# design.net
KiCad netlist of a schematic drawn in Altium Designer
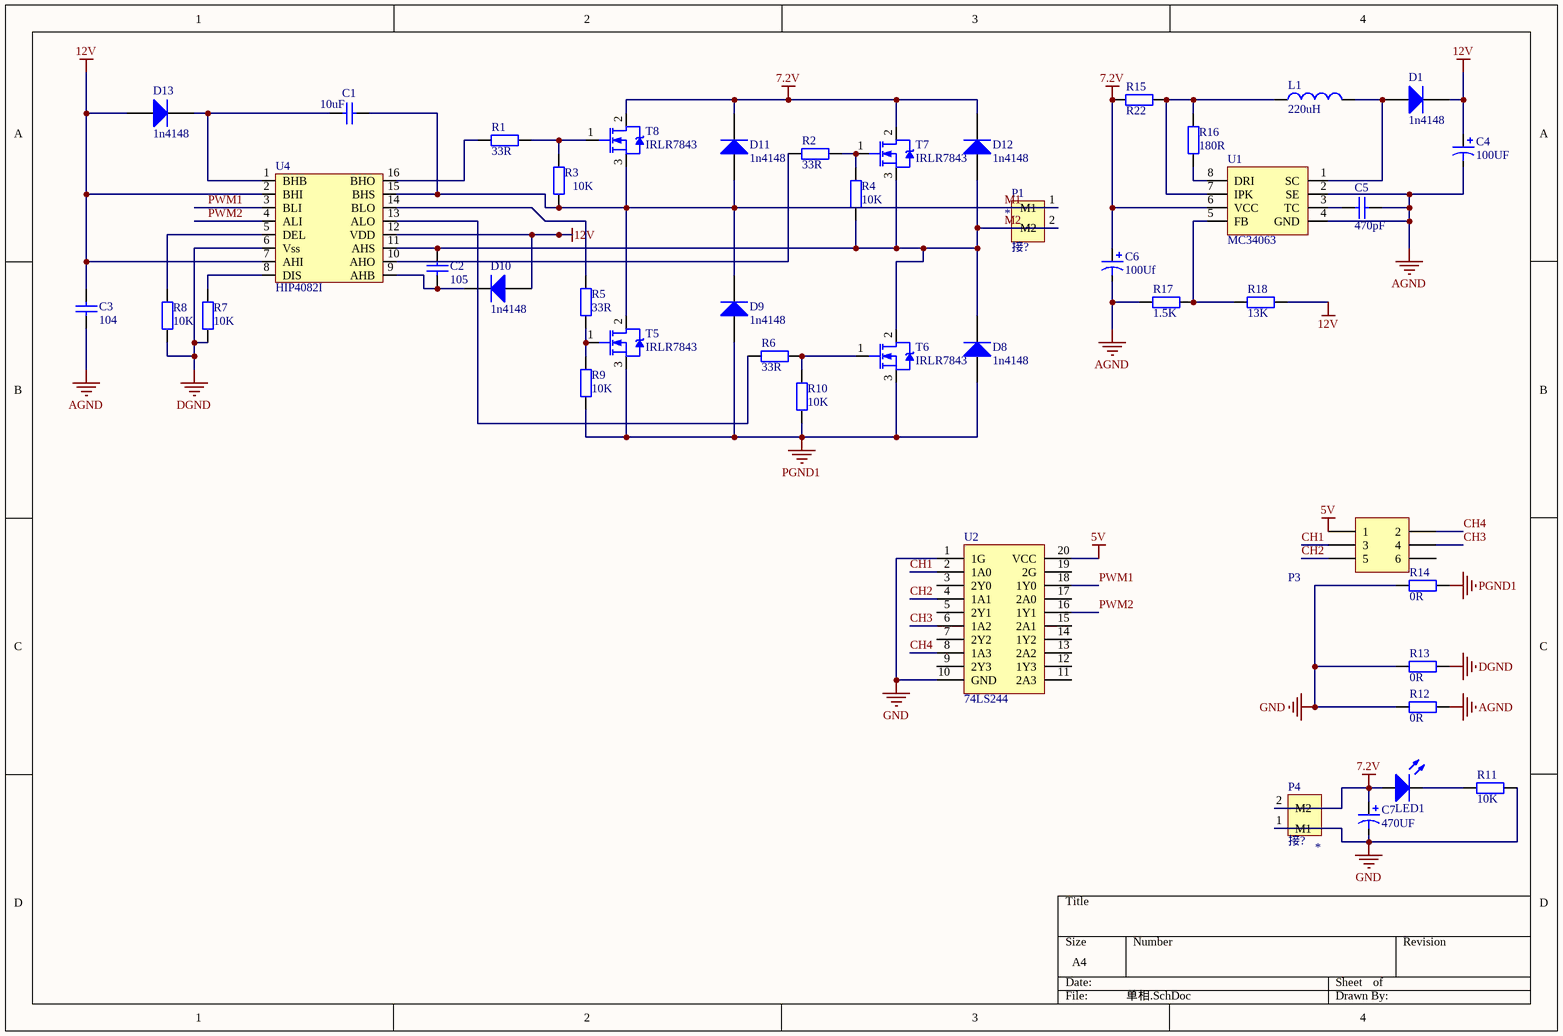
[diagram p0: 单相.SchDoc]

(export (version "E")
  (design (tool "Eeschema 10.0.6"))
  (components
    (comp (ref "C1")
      (value "10uF")
      (footprint "0805")
      (description "无极电容")
      (fields (field (name "Comment") "105"))
      (libsource (lib "JMU智能车专用3.0.6") (part "Cap"))
    )
    (comp (ref "C2")
      (value "105")
      (footprint "0805")
      (description "无极电容")
      (libsource (lib "JMU智能车专用3.0.6") (part "Cap"))
    )
    (comp (ref "C3")
      (value "104")
      (footprint "0805")
      (description "无极电容")
      (libsource (lib "JMU智能车专用3.0.6") (part "Cap"))
    )
    (comp (ref "C4")
      (value "100UF")
      (footprint "ED6.3")
      (description "通用有极电容")
      (libsource (lib "JMU智能车专用3.0.6") (part "pol cap"))
    )
    (comp (ref "C5")
      (value "470pF")
      (footprint "0805")
      (description "无极电容")
      (libsource (lib "JMU智能车专用3.0.6") (part "Cap"))
    )
    (comp (ref "C6")
      (value "100Uf")
      (footprint "ED6.3")
      (description "通用有极电容")
      (libsource (lib "JMU智能车专用3.0.6") (part "pol cap"))
    )
    (comp (ref "C7")
      (value "470UF")
      (footprint "ED8")
      (description "通用有极电容")
      (libsource (lib "JMU智能车专用3.0.6") (part "pol cap"))
    )
    (comp (ref "D1") (value "1n4148") (libsource (lib "zaji") (part "1n4148")))
    (comp (ref "D8") (value "1n4148") (libsource (lib "zaji") (part "1n4148")))
    (comp (ref "D9") (value "1n4148") (libsource (lib "zaji") (part "1n4148")))
    (comp (ref "D10") (value "1n4148") (libsource (lib "zaji") (part "1n4148")))
    (comp (ref "D11") (value "1n4148") (libsource (lib "zaji") (part "1n4148")))
    (comp (ref "D12") (value "1n4148") (libsource (lib "zaji") (part "1n4148")))
    (comp (ref "D13") (value "1n4148") (libsource (lib "zaji") (part "1n4148")))
    (comp (ref "L1")
      (value "220uH")
      (footprint "电感（220uh）")
      (description "7*7*4")
      (libsource (lib "JMU智能车专用3.0.6") (part "电感 220uh"))
    )
    (comp (ref "LED1")
      (value "LED")
      (footprint "LED(0805)")
      (description "发光二极管")
      (libsource (lib "JMU智能车专用3.0.6") (part "LED"))
    )
    (comp (ref "P1")
      (value "*")
      (fields (field (name "ALTIUM_UNNAMED_3") "接?"))
      (libsource (lib "JMU智能车专用") (part "接线端子"))
    )
    (comp (ref "P3")
      (value "Header 3X2")
      (footprint "HDR2X3")
      (description "Header, 3-Pin, Dual row")
      (fields (field (name "PUBLISHER") "Altium Limited"))
      (libsource (lib "Miscellaneous Connectors") (part "Header 3X2"))
    )
    (comp (ref "P4")
      (value "*")
      (fields (field (name "ALTIUM_UNNAMED_3") "接?"))
      (libsource (lib "") (part "接线端子_1"))
    )
    (comp (ref "R1")
      (value "33R")
      (footprint "0805")
      (description "通用电阻")
      (libsource (lib "") (part "Res_2"))
    )
    (comp (ref "R2")
      (value "33R")
      (footprint "0805")
      (description "通用电阻")
      (libsource (lib "") (part "Res_1"))
    )
    (comp (ref "R3")
      (value "10K")
      (footprint "0805")
      (description "通用电阻")
      (libsource (lib "JMU智能车专用") (part "Res"))
    )
    (comp (ref "R4")
      (value "10K")
      (footprint "0805")
      (description "通用电阻")
      (libsource (lib "JMU智能车专用") (part "Res"))
    )
    (comp (ref "R5")
      (value "33R")
      (footprint "0805")
      (description "通用电阻")
      (libsource (lib "") (part "Res_3"))
    )
    (comp (ref "R6")
      (value "33R")
      (footprint "0805")
      (description "通用电阻")
      (libsource (lib "") (part "Res_1"))
    )
    (comp (ref "R7")
      (value "10K")
      (footprint "0805")
      (description "通用电阻")
      (libsource (lib "") (part "Res_3"))
    )
    (comp (ref "R8")
      (value "10K")
      (footprint "0805")
      (description "通用电阻")
      (libsource (lib "") (part "Res_3"))
    )
    (comp (ref "R9")
      (value "10K")
      (footprint "0805")
      (description "通用电阻")
      (libsource (lib "JMU智能车专用") (part "Res"))
    )
    (comp (ref "R10")
      (value "10K")
      (footprint "0805")
      (description "通用电阻")
      (libsource (lib "") (part "Res_3"))
    )
    (comp (ref "R11")
      (value "10K")
      (footprint "0603")
      (description "通用电阻")
      (libsource (lib "") (part "Res_1"))
    )
    (comp (ref "R12")
      (value "0R")
      (footprint "0805")
      (description "通用电阻")
      (libsource (lib "") (part "Res_2"))
    )
    (comp (ref "R13")
      (value "0R")
      (footprint "0805")
      (description "通用电阻")
      (libsource (lib "") (part "Res_2"))
    )
    (comp (ref "R14")
      (value "0R")
      (footprint "0805")
      (description "通用电阻")
      (libsource (lib "") (part "Res_2"))
    )
    (comp (ref "R15")
      (value "R22")
      (footprint "0805")
      (description "通用电阻")
      (libsource (lib "JMU智能车专用3.0.6") (part "Res"))
    )
    (comp (ref "R16")
      (value "180R")
      (footprint "0805")
      (description "通用电阻")
      (libsource (lib "") (part "Res_2"))
    )
    (comp (ref "R17")
      (value "1.5K")
      (footprint "0805")
      (description "通用电阻")
      (libsource (lib "JMU智能车专用3.0.6") (part "Res"))
    )
    (comp (ref "R18")
      (value "13K")
      (footprint "0805")
      (description "通用电阻")
      (libsource (lib "JMU智能车专用3.0.6") (part "Res"))
    )
    (comp (ref "T5")
      (value "IRLR7843")
      (footprint "IRLR7843(MOS)")
      (libsource (lib "JMU智能车专用") (part "N_MOS(IRLR7843)"))
    )
    (comp (ref "T6")
      (value "IRLR7843")
      (footprint "IRLR7843(MOS)")
      (libsource (lib "JMU智能车专用") (part "N_MOS(IRLR7843)"))
    )
    (comp (ref "T7")
      (value "IRLR7843")
      (footprint "IRLR7843(MOS)")
      (libsource (lib "JMU智能车专用") (part "N_MOS(IRLR7843)"))
    )
    (comp (ref "T8")
      (value "IRLR7843")
      (footprint "IRLR7843(MOS)")
      (libsource (lib "JMU智能车专用") (part "N_MOS(IRLR7843)"))
    )
    (comp (ref "U1")
      (value "MC34063")
      (footprint "MA34063")
      (libsource (lib "JMU智能车专用3.0.6") (part "MC34063"))
    )
    (comp (ref "U2")
      (value "74LS244")
      (footprint "74LS244D")
      (libsource (lib "JMU智能车专用3.0.6") (part "74LS244"))
    )
    (comp (ref "U4") (value "HIP4082I") (footprint "HIP4082I") (libsource (lib "JMU智能车专用") (part "HIP4082I")))
  )
  (nets
    (net (code "1") (name "/CH1") (class "Default")
      (node (ref "P3") (pin "3") (pinfunction "3_3") (pintype "passive"))
      (node (ref "U2") (pin "2") (pinfunction "1A0_2") (pintype "passive"))
    )
    (net (code "2") (name "/CH2") (class "Default")
      (node (ref "P3") (pin "5") (pinfunction "5_5") (pintype "passive"))
      (node (ref "U2") (pin "4") (pinfunction "1A1_4") (pintype "passive"))
    )
    (net (code "3") (name "/CH3") (class "Default")
      (node (ref "P3") (pin "4") (pinfunction "4_4") (pintype "passive"))
      (node (ref "U2") (pin "6") (pinfunction "1A2_6") (pintype "passive"))
    )
    (net (code "4") (name "/CH4") (class "Default")
      (node (ref "P3") (pin "2") (pinfunction "2_2") (pintype "passive"))
      (node (ref "U2") (pin "8") (pinfunction "1A3_8") (pintype "passive"))
    )
    (net (code "5") (name "/M1") (class "Default")
      (node (ref "C1") (pin "2") (pinfunction "2_2") (pintype "passive"))
      (node (ref "D11") (pin "1") (pinfunction "A_1") (pintype "passive"))
      (node (ref "D9") (pin "2") (pinfunction "K_2") (pintype "passive"))
      (node (ref "P1") (pin "1") (pinfunction "M1_1") (pintype "passive"))
      (node (ref "R3") (pin "2") (pinfunction "2_2") (pintype "passive"))
      (node (ref "T5") (pin "2") (pinfunction "D_2") (pintype "passive"))
      (node (ref "T8") (pin "3") (pinfunction "S_3") (pintype "passive"))
      (node (ref "U4") (pin "15") (pinfunction "BHS_15") (pintype "passive"))
    )
    (net (code "6") (name "/M2") (class "Default")
      (node (ref "C2") (pin "2") (pinfunction "2_2") (pintype "passive"))
      (node (ref "D12") (pin "1") (pinfunction "A_1") (pintype "passive"))
      (node (ref "D8") (pin "2") (pinfunction "K_2") (pintype "passive"))
      (node (ref "P1") (pin "2") (pinfunction "M2_2") (pintype "passive"))
      (node (ref "R4") (pin "2") (pinfunction "2_2") (pintype "passive"))
      (node (ref "T6") (pin "2") (pinfunction "D_2") (pintype "passive"))
      (node (ref "T7") (pin "3") (pinfunction "S_3") (pintype "passive"))
      (node (ref "U4") (pin "11") (pinfunction "AHS_11") (pintype "passive"))
    )
    (net (code "7") (name "/PWM1") (class "Default")
      (node (ref "U2") (pin "18") (pinfunction "1Y0_18") (pintype "passive"))
      (node (ref "U4") (pin "3") (pinfunction "BLI_3") (pintype "passive"))
    )
    (net (code "8") (name "/PWM2") (class "Default")
      (node (ref "U2") (pin "16") (pinfunction "1Y1_16") (pintype "passive"))
      (node (ref "U4") (pin "4") (pinfunction "ALI_4") (pintype "passive"))
    )
    (net (code "9") (name "5V") (class "Default")
      (node (ref "P3") (pin "1") (pinfunction "1_1") (pintype "passive"))
      (node (ref "U2") (pin "20") (pinfunction "VCC_20") (pintype "passive"))
    )
    (net (code "10") (name "7.2V") (class "Default")
      (node (ref "C6") (pin "1") (pinfunction "1_1") (pintype "passive"))
      (node (ref "C7") (pin "1") (pinfunction "1_1") (pintype "passive"))
      (node (ref "D11") (pin "2") (pinfunction "K_2") (pintype "passive"))
      (node (ref "D12") (pin "2") (pinfunction "K_2") (pintype "passive"))
      (node (ref "LED1") (pin "1") (pinfunction "A_1") (pintype "passive"))
      (node (ref "P4") (pin "2") (pinfunction "M2_2") (pintype "passive"))
      (node (ref "R15") (pin "1") (pinfunction "1_1") (pintype "passive"))
      (node (ref "T7") (pin "2") (pinfunction "D_2") (pintype "passive"))
      (node (ref "T8") (pin "2") (pinfunction "D_2") (pintype "passive"))
      (node (ref "U1") (pin "6") (pinfunction "VCC_6") (pintype "passive"))
    )
    (net (code "11") (name "12V") (class "Default")
      (node (ref "C3") (pin "2") (pinfunction "2_2") (pintype "passive"))
      (node (ref "C4") (pin "1") (pinfunction "1_1") (pintype "passive"))
      (node (ref "D1") (pin "2") (pinfunction "K_2") (pintype "passive"))
      (node (ref "D10") (pin "1") (pinfunction "A_1") (pintype "passive"))
      (node (ref "D13") (pin "1") (pinfunction "A_1") (pintype "passive"))
      (node (ref "R18") (pin "2") (pinfunction "2_2") (pintype "passive"))
      (node (ref "U4") (pin "12") (pinfunction "VDD_12") (pintype "passive"))
      (node (ref "U4") (pin "2") (pinfunction "BHI_2") (pintype "passive"))
      (node (ref "U4") (pin "7") (pinfunction "AHI_7") (pintype "passive"))
    )
    (net (code "12") (name "AGND") (class "Default")
      (node (ref "C3") (pin "1") (pinfunction "1_1") (pintype "passive"))
      (node (ref "C4") (pin "2") (pinfunction "2_2") (pintype "passive"))
      (node (ref "C5") (pin "1") (pinfunction "1_1") (pintype "passive"))
      (node (ref "C6") (pin "2") (pinfunction "2_2") (pintype "passive"))
      (node (ref "R12") (pin "2") (pinfunction "2_2") (pintype "passive"))
      (node (ref "R17") (pin "1") (pinfunction "1_1") (pintype "passive"))
      (node (ref "U1") (pin "2") (pinfunction "SE_2") (pintype "passive"))
      (node (ref "U1") (pin "4") (pinfunction "GND_4") (pintype "passive"))
    )
    (net (code "13") (name "DGND") (class "Default")
      (node (ref "R13") (pin "2") (pinfunction "2_2") (pintype "passive"))
      (node (ref "R7") (pin "1") (pinfunction "1_1") (pintype "passive"))
      (node (ref "R8") (pin "1") (pinfunction "1_1") (pintype "passive"))
      (node (ref "U4") (pin "6") (pinfunction "Vss_6") (pintype "passive"))
    )
    (net (code "14") (name "GND") (class "Default")
      (node (ref "C7") (pin "2") (pinfunction "2_2") (pintype "passive"))
      (node (ref "P4") (pin "1") (pinfunction "M1_1") (pintype "passive"))
      (node (ref "R11") (pin "1") (pinfunction "1_1") (pintype "passive"))
      (node (ref "R12") (pin "1") (pinfunction "1_1") (pintype "passive"))
      (node (ref "R13") (pin "1") (pinfunction "1_1") (pintype "passive"))
      (node (ref "R14") (pin "1") (pinfunction "1_1") (pintype "passive"))
      (node (ref "U2") (pin "1") (pinfunction "1G_1") (pintype "passive"))
      (node (ref "U2") (pin "10") (pinfunction "GND_10") (pintype "passive"))
    )
    (net (code "15") (name "Net-(D1-A)") (class "Default")
      (node (ref "D1") (pin "1") (pinfunction "A_1") (pintype "passive"))
      (node (ref "L1") (pin "2") (pinfunction "2_2") (pintype "passive"))
      (node (ref "U1") (pin "1") (pinfunction "SC_1") (pintype "passive"))
    )
    (net (code "16") (name "Net-(D10-K)") (class "Default")
      (node (ref "C2") (pin "1") (pinfunction "1_1") (pintype "passive"))
      (node (ref "D10") (pin "2") (pinfunction "K_2") (pintype "passive"))
      (node (ref "U4") (pin "9") (pinfunction "AHB_9") (pintype "passive"))
    )
    (net (code "17") (name "Net-(D13-K)") (class "Default")
      (node (ref "C1") (pin "1") (pinfunction "1_1") (pintype "passive"))
      (node (ref "D13") (pin "2") (pinfunction "K_2") (pintype "passive"))
      (node (ref "U4") (pin "1") (pinfunction "BHB_1") (pintype "passive"))
    )
    (net (code "18") (name "Net-(LED1-K)") (class "Default")
      (node (ref "LED1") (pin "2") (pinfunction "K_2") (pintype "passive"))
      (node (ref "R11") (pin "2") (pinfunction "2_2") (pintype "passive"))
    )
    (net (code "19") (name "Net-(T5-G)") (class "Default")
      (node (ref "R5") (pin "1") (pinfunction "1_1") (pintype "passive"))
      (node (ref "R9") (pin "1") (pinfunction "1_1") (pintype "passive"))
      (node (ref "T5") (pin "1") (pinfunction "G_1") (pintype "passive"))
    )
    (net (code "20") (name "Net-(T6-G)") (class "Default")
      (node (ref "R10") (pin "2") (pinfunction "2_2") (pintype "passive"))
      (node (ref "R6") (pin "1") (pinfunction "1_1") (pintype "passive"))
      (node (ref "T6") (pin "1") (pinfunction "G_1") (pintype "passive"))
    )
    (net (code "21") (name "Net-(T7-G)") (class "Default")
      (node (ref "R2") (pin "1") (pinfunction "1_1") (pintype "passive"))
      (node (ref "R4") (pin "1") (pinfunction "1_1") (pintype "passive"))
      (node (ref "T7") (pin "1") (pinfunction "G_1") (pintype "passive"))
    )
    (net (code "22") (name "Net-(T8-G)") (class "Default")
      (node (ref "R1") (pin "2") (pinfunction "2_2") (pintype "passive"))
      (node (ref "R3") (pin "1") (pinfunction "1_1") (pintype "passive"))
      (node (ref "T8") (pin "1") (pinfunction "G_1") (pintype "passive"))
    )
    (net (code "23") (name "Net-(U1-DRI)") (class "Default")
      (node (ref "R16") (pin "1") (pinfunction "1_1") (pintype "passive"))
      (node (ref "U1") (pin "8") (pinfunction "DRI_8") (pintype "passive"))
    )
    (net (code "24") (name "Net-(U1-FB)") (class "Default")
      (node (ref "R17") (pin "2") (pinfunction "2_2") (pintype "passive"))
      (node (ref "R18") (pin "1") (pinfunction "1_1") (pintype "passive"))
      (node (ref "U1") (pin "5") (pinfunction "FB_5") (pintype "passive"))
    )
    (net (code "25") (name "Net-(U1-IPK)") (class "Default")
      (node (ref "L1") (pin "1") (pinfunction "1_1") (pintype "passive"))
      (node (ref "R15") (pin "2") (pinfunction "2_2") (pintype "passive"))
      (node (ref "R16") (pin "2") (pinfunction "2_2") (pintype "passive"))
      (node (ref "U1") (pin "7") (pinfunction "IPK_7") (pintype "passive"))
    )
    (net (code "26") (name "Net-(U1-TC)") (class "Default")
      (node (ref "C5") (pin "2") (pinfunction "2_2") (pintype "passive"))
      (node (ref "U1") (pin "3") (pinfunction "TC_3") (pintype "passive"))
    )
    (net (code "27") (name "Net-(U4-AHO)") (class "Default")
      (node (ref "R2") (pin "2") (pinfunction "2_2") (pintype "passive"))
      (node (ref "U4") (pin "10") (pinfunction "AHO_10") (pintype "passive"))
    )
    (net (code "28") (name "Net-(U4-ALO)") (class "Default")
      (node (ref "R6") (pin "2") (pinfunction "2_2") (pintype "passive"))
      (node (ref "U4") (pin "13") (pinfunction "ALO_13") (pintype "passive"))
    )
    (net (code "29") (name "Net-(U4-BHO)") (class "Default")
      (node (ref "R1") (pin "1") (pinfunction "1_1") (pintype "passive"))
      (node (ref "U4") (pin "16") (pinfunction "BHO_16") (pintype "passive"))
    )
    (net (code "30") (name "Net-(U4-BLO)") (class "Default")
      (node (ref "R5") (pin "2") (pinfunction "2_2") (pintype "passive"))
      (node (ref "U4") (pin "14") (pinfunction "BLO_14") (pintype "passive"))
    )
    (net (code "31") (name "Net-(U4-DEL)") (class "Default")
      (node (ref "R8") (pin "2") (pinfunction "2_2") (pintype "passive"))
      (node (ref "U4") (pin "5") (pinfunction "DEL_5") (pintype "passive"))
    )
    (net (code "32") (name "Net-(U4-DIS)") (class "Default")
      (node (ref "R7") (pin "2") (pinfunction "2_2") (pintype "passive"))
      (node (ref "U4") (pin "8") (pinfunction "DIS_8") (pintype "passive"))
    )
    (net (code "33") (name "PGND1") (class "Default")
      (node (ref "D8") (pin "1") (pinfunction "A_1") (pintype "passive"))
      (node (ref "D9") (pin "1") (pinfunction "A_1") (pintype "passive"))
      (node (ref "R10") (pin "1") (pinfunction "1_1") (pintype "passive"))
      (node (ref "R14") (pin "2") (pinfunction "2_2") (pintype "passive"))
      (node (ref "R9") (pin "2") (pinfunction "2_2") (pintype "passive"))
      (node (ref "T5") (pin "3") (pinfunction "S_3") (pintype "passive"))
      (node (ref "T6") (pin "3") (pinfunction "S_3") (pintype "passive"))
    )
    (net (code "34") (name "unconnected-(P3-Pad6)") (class "Default")
      (node (ref "P3") (pin "6") (pinfunction "6_6") (pintype "passive"))
    )
    (net (code "35") (name "unconnected-(U2-1Y2-Pad14)") (class "Default")
      (node (ref "U2") (pin "14") (pinfunction "1Y2_14") (pintype "passive"))
    )
    (net (code "36") (name "unconnected-(U2-1Y3-Pad12)") (class "Default")
      (node (ref "U2") (pin "12") (pinfunction "1Y3_12") (pintype "passive"))
    )
    (net (code "37") (name "unconnected-(U2-2A0-Pad17)") (class "Default")
      (node (ref "U2") (pin "17") (pinfunction "2A0_17") (pintype "passive"))
    )
    (net (code "38") (name "unconnected-(U2-2A1-Pad15)") (class "Default")
      (node (ref "U2") (pin "15") (pinfunction "2A1_15") (pintype "passive"))
    )
    (net (code "39") (name "unconnected-(U2-2A2-Pad13)") (class "Default")
      (node (ref "U2") (pin "13") (pinfunction "2A2_13") (pintype "passive"))
    )
    (net (code "40") (name "unconnected-(U2-2A3-Pad11)") (class "Default")
      (node (ref "U2") (pin "11") (pinfunction "2A3_11") (pintype "passive"))
    )
    (net (code "41") (name "unconnected-(U2-2G-Pad19)") (class "Default")
      (node (ref "U2") (pin "19") (pinfunction "2G_19") (pintype "passive"))
    )
    (net (code "42") (name "unconnected-(U2-2Y0-Pad3)") (class "Default")
      (node (ref "U2") (pin "3") (pinfunction "2Y0_3") (pintype "passive"))
    )
    (net (code "43") (name "unconnected-(U2-2Y1-Pad5)") (class "Default")
      (node (ref "U2") (pin "5") (pinfunction "2Y1_5") (pintype "passive"))
    )
    (net (code "44") (name "unconnected-(U2-2Y2-Pad7)") (class "Default")
      (node (ref "U2") (pin "7") (pinfunction "2Y2_7") (pintype "passive"))
    )
    (net (code "45") (name "unconnected-(U2-2Y3-Pad9)") (class "Default")
      (node (ref "U2") (pin "9") (pinfunction "2Y3_9") (pintype "passive"))
    )
  )
)
